# wb_imx233_core_rev_c3.net
KiCad netlist of a schematic drawn in EAGLE
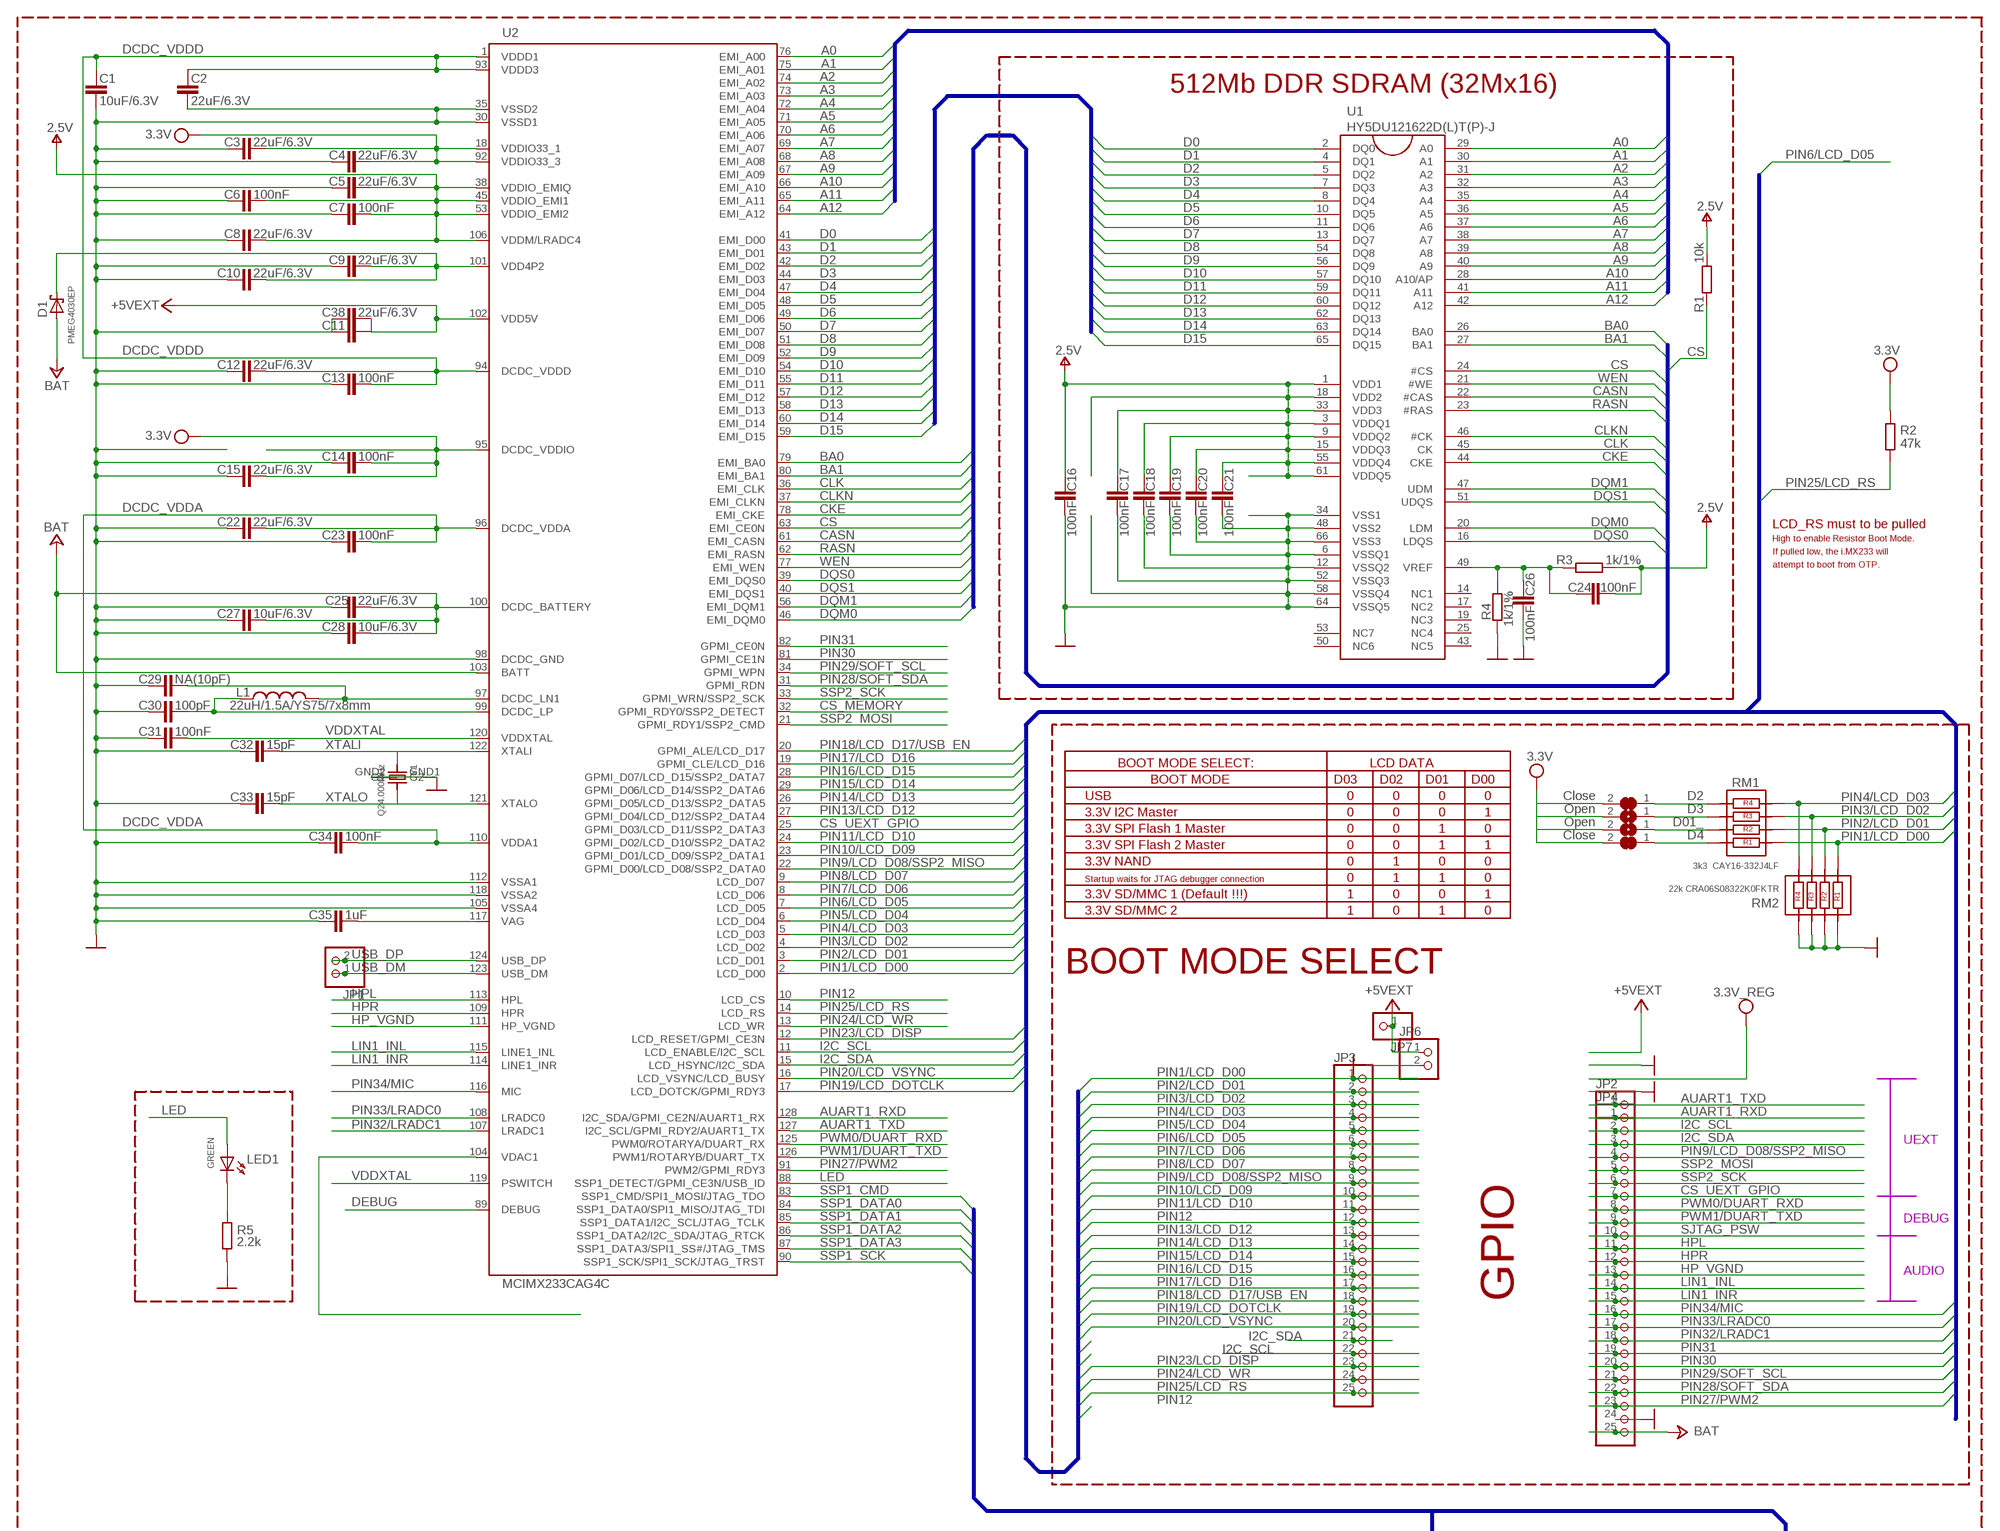
[diagram p0: schematic, sheet 1, part 1 of 2]
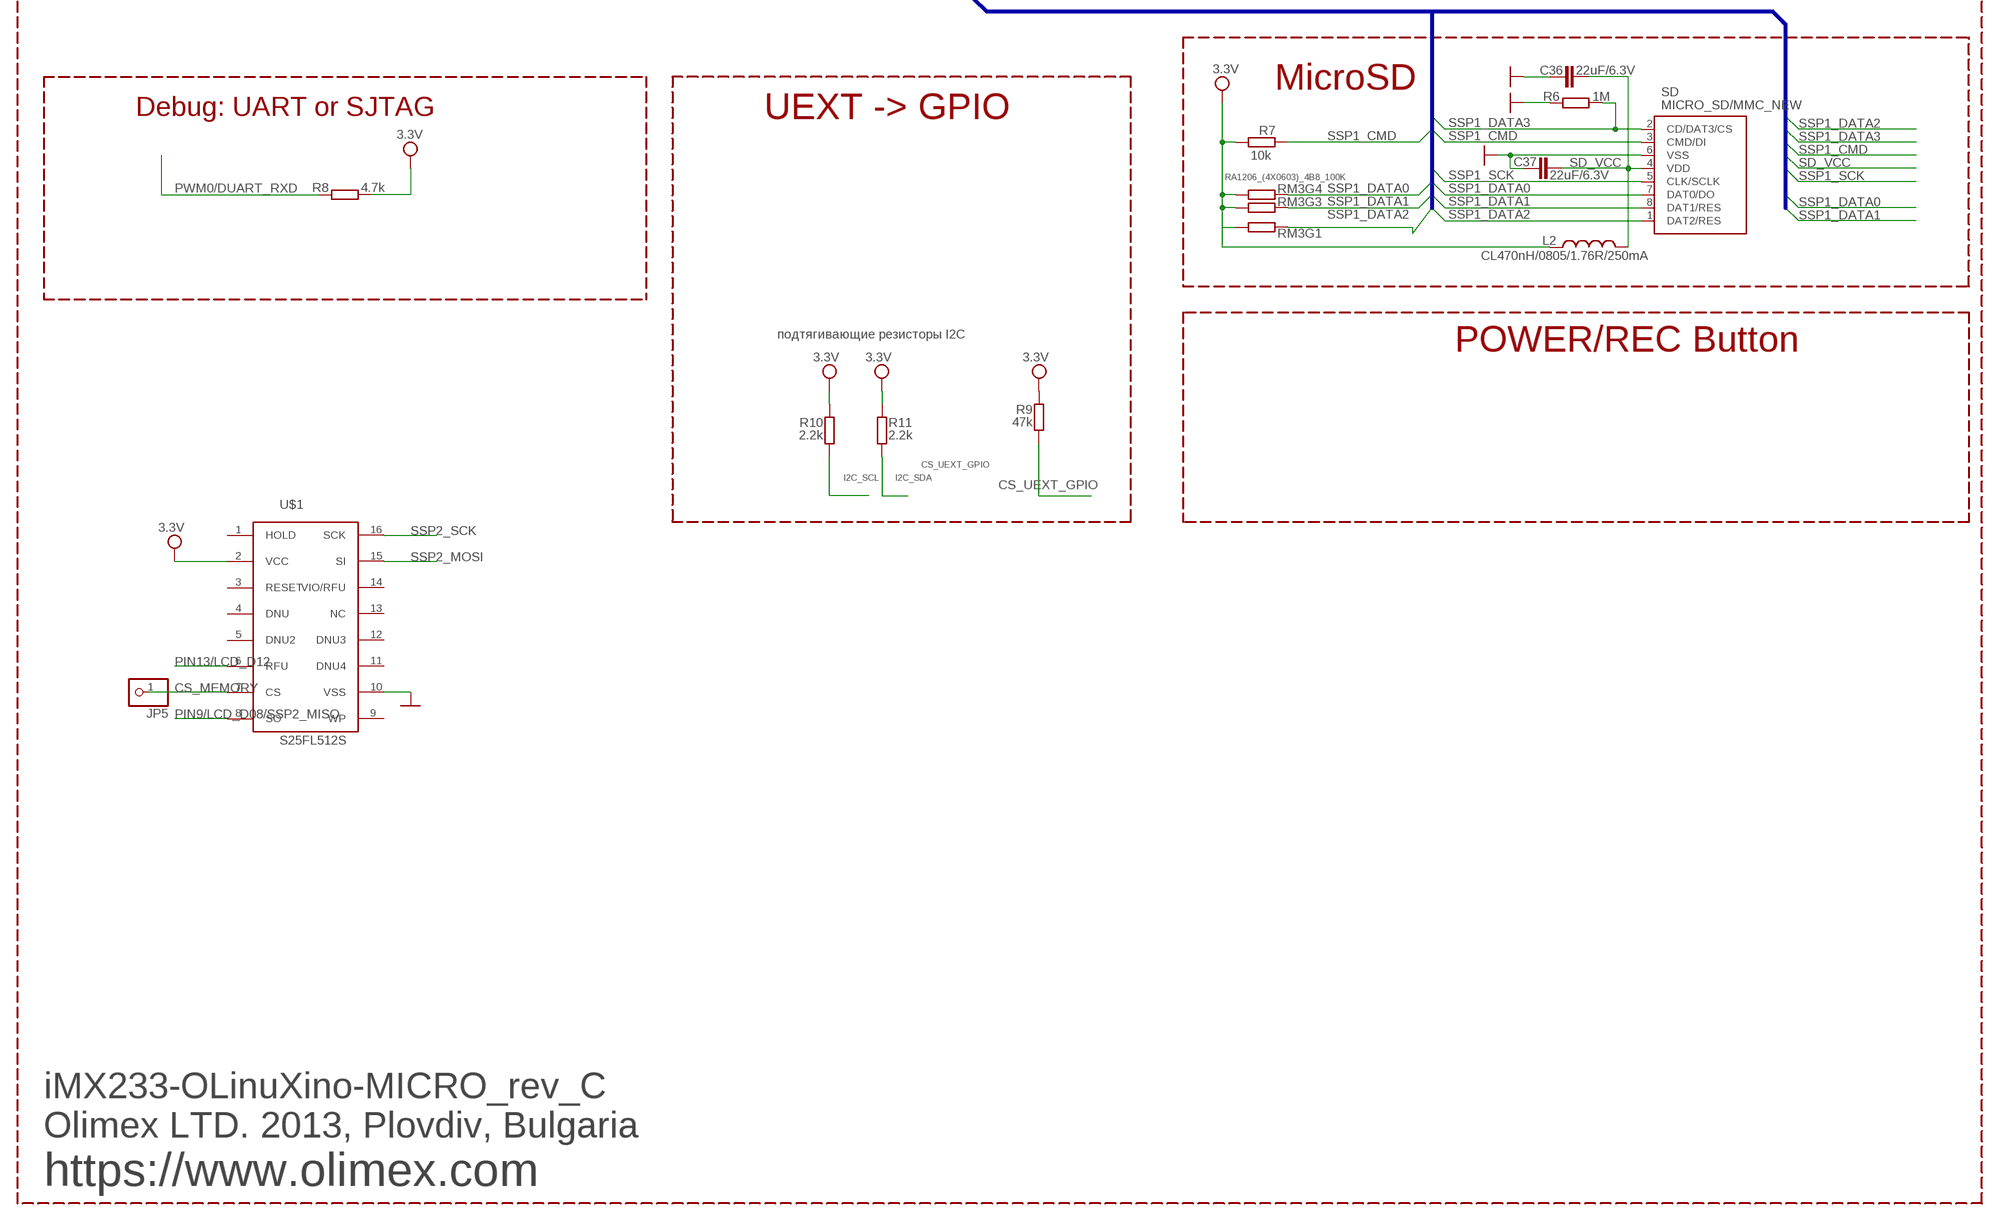
[diagram p1: schematic, sheet 1, part 2 of 2]

(export (version "E")
  (design (tool "Eeschema 10.0.6"))
  (components
    (comp (ref "C1")
      (value "10uF/6.3V")
      (footprint "eagle-import:C0603_DWS")
      (libsource (lib "eagle-import") (part "C-EUC0603_DWS"))
    )
    (comp (ref "C2")
      (value "22uF/6.3V")
      (footprint "eagle-import:C0603_DWS")
      (libsource (lib "eagle-import") (part "C-EUC0603_DWS"))
    )
    (comp (ref "C3")
      (value "22uF/6.3V")
      (footprint "eagle-import:C0603_DWS")
      (libsource (lib "eagle-import") (part "C-EUC0603_DWS"))
    )
    (comp (ref "C4")
      (value "22uF/6.3V")
      (footprint "eagle-import:C0603_DWS")
      (libsource (lib "eagle-import") (part "C-EUC0603_DWS"))
    )
    (comp (ref "C5")
      (value "22uF/6.3V")
      (footprint "eagle-import:C0603_DWS")
      (libsource (lib "eagle-import") (part "C-EUC0603_DWS"))
    )
    (comp (ref "C6")
      (value "100nF")
      (footprint "eagle-import:C0603_DWS")
      (libsource (lib "eagle-import") (part "C-EUC0603_DWS"))
    )
    (comp (ref "C7")
      (value "100nF")
      (footprint "eagle-import:C0603_DWS")
      (libsource (lib "eagle-import") (part "C-EUC0603_DWS"))
    )
    (comp (ref "C8")
      (value "22uF/6.3V")
      (footprint "eagle-import:C0603_DWS")
      (libsource (lib "eagle-import") (part "C-EUC0603_DWS"))
    )
    (comp (ref "C9")
      (value "22uF/6.3V")
      (footprint "eagle-import:C0603_DWS")
      (libsource (lib "eagle-import") (part "C-EUC0603_DWS"))
    )
    (comp (ref "C10")
      (value "22uF/6.3V")
      (footprint "eagle-import:C0603_DWS")
      (libsource (lib "eagle-import") (part "C-EUC0603_DWS"))
    )
    (comp (ref "C11")
      (value "100nF")
      (footprint "eagle-import:C0603_DWS")
      (libsource (lib "eagle-import") (part "C-EUC0603_DWS"))
    )
    (comp (ref "C12")
      (value "22uF/6.3V")
      (footprint "eagle-import:C0603_DWS")
      (libsource (lib "eagle-import") (part "C-EUC0603_DWS"))
    )
    (comp (ref "C13")
      (value "100nF")
      (footprint "eagle-import:C0603_DWS")
      (libsource (lib "eagle-import") (part "C-EUC0603_DWS"))
    )
    (comp (ref "C14")
      (value "100nF")
      (footprint "eagle-import:C0603_DWS")
      (libsource (lib "eagle-import") (part "C-EUC0603_DWS"))
    )
    (comp (ref "C15")
      (value "22uF/6.3V")
      (footprint "eagle-import:C0603_DWS")
      (libsource (lib "eagle-import") (part "C-EUC0603_DWS"))
    )
    (comp (ref "C16")
      (value "100nF")
      (footprint "eagle-import:C0603_DWS")
      (libsource (lib "eagle-import") (part "C-EUC0603_DWS"))
    )
    (comp (ref "C17")
      (value "100nF")
      (footprint "eagle-import:C0603_DWS")
      (libsource (lib "eagle-import") (part "C-EUC0603_DWS"))
    )
    (comp (ref "C18")
      (value "100nF")
      (footprint "eagle-import:C0603_DWS")
      (libsource (lib "eagle-import") (part "C-EUC0603_DWS"))
    )
    (comp (ref "C19")
      (value "100nF")
      (footprint "eagle-import:C0603_DWS")
      (libsource (lib "eagle-import") (part "C-EUC0603_DWS"))
    )
    (comp (ref "C20")
      (value "100nF")
      (footprint "eagle-import:C0603_DWS")
      (libsource (lib "eagle-import") (part "C-EUC0603_DWS"))
    )
    (comp (ref "C21")
      (value "100nF")
      (footprint "eagle-import:C0603_DWS")
      (libsource (lib "eagle-import") (part "C-EUC0603_DWS"))
    )
    (comp (ref "C22")
      (value "22uF/6.3V")
      (footprint "eagle-import:C0603_DWS")
      (libsource (lib "eagle-import") (part "C-EUC0603_DWS"))
    )
    (comp (ref "C23")
      (value "100nF")
      (footprint "eagle-import:C0603_DWS")
      (libsource (lib "eagle-import") (part "C-EUC0603_DWS"))
    )
    (comp (ref "C24")
      (value "100nF")
      (footprint "eagle-import:C0603_DWS")
      (libsource (lib "eagle-import") (part "C-EUC0603_DWS"))
    )
    (comp (ref "C25")
      (value "22uF/6.3V")
      (footprint "eagle-import:C0603_DWS")
      (libsource (lib "eagle-import") (part "C-EUC0603_DWS"))
    )
    (comp (ref "C26")
      (value "100nF")
      (footprint "eagle-import:C0603_DWS")
      (libsource (lib "eagle-import") (part "C-EUC0603_DWS"))
    )
    (comp (ref "C27")
      (value "10uF/6.3V")
      (footprint "eagle-import:C0603_DWS")
      (libsource (lib "eagle-import") (part "C-EUC0603_DWS"))
    )
    (comp (ref "C28")
      (value "10uF/6.3V")
      (footprint "eagle-import:C0603_DWS")
      (libsource (lib "eagle-import") (part "C-EUC0603_DWS"))
    )
    (comp (ref "C29")
      (value "NA(10pF)")
      (footprint "eagle-import:C0603_DWS")
      (libsource (lib "eagle-import") (part "C-EUC0603_DWS"))
    )
    (comp (ref "C30")
      (value "100pF")
      (footprint "eagle-import:C0603_DWS")
      (libsource (lib "eagle-import") (part "C-EUC0603_DWS"))
    )
    (comp (ref "C31")
      (value "100nF")
      (footprint "eagle-import:C0603_DWS")
      (libsource (lib "eagle-import") (part "C-EUC0603_DWS"))
    )
    (comp (ref "C32")
      (value "15pF")
      (footprint "eagle-import:C0603_DWS")
      (libsource (lib "eagle-import") (part "C-EUC0603_DWS"))
    )
    (comp (ref "C33")
      (value "15pF")
      (footprint "eagle-import:C0603_DWS")
      (libsource (lib "eagle-import") (part "C-EUC0603_DWS"))
    )
    (comp (ref "C34")
      (value "100nF")
      (footprint "eagle-import:C0603_DWS")
      (libsource (lib "eagle-import") (part "C-EUC0603_DWS"))
    )
    (comp (ref "C35")
      (value "1uF")
      (footprint "eagle-import:C0603_DWS")
      (libsource (lib "eagle-import") (part "C-EUC0603_DWS"))
    )
    (comp (ref "C36")
      (value "22uF/6.3V")
      (footprint "eagle-import:C0603_DWS")
      (libsource (lib "eagle-import") (part "C-EUC0603_DWS"))
    )
    (comp (ref "C37")
      (value "22uF/6.3V")
      (footprint "eagle-import:C0603_DWS")
      (libsource (lib "eagle-import") (part "C-EUC0603_DWS"))
    )
    (comp (ref "C38")
      (value "22uF/6.3V")
      (footprint "eagle-import:C0603_DWS")
      (libsource (lib "eagle-import") (part "C-EUC0603_DWS"))
    )
    (comp (ref "D1")
      (value "PMEG4030EP")
      (footprint "eagle-import:MLL-41")
      (libsource (lib "eagle-import") (part "SCHOTKKY7.62SS2"))
    )
    (comp (ref "D01_")
      (value "Open")
      (footprint "eagle-import:SJ_1_SMALLER")
      (libsource (lib "eagle-import") (part "SJSJ_SMALLER"))
    )
    (comp (ref "D2")
      (value "Close")
      (footprint "eagle-import:SJ_1_SMALLER")
      (libsource (lib "eagle-import") (part "SJSJ_SMALLER"))
    )
    (comp (ref "D3")
      (value "Open")
      (footprint "eagle-import:SJ_1_SMALLER")
      (libsource (lib "eagle-import") (part "SJSJ_SMALLER"))
    )
    (comp (ref "D4")
      (value "Close")
      (footprint "eagle-import:SJ_1_SMALLER")
      (libsource (lib "eagle-import") (part "SJSJ_SMALLER"))
    )
    (comp (ref "JP1")
      (value "PINHD-1X2")
      (footprint "eagle-import:1X02-R")
      (libsource (lib "eagle-import") (part "PINHD-1X2"))
    )
    (comp (ref "JP2")
      (value "PINHD-1X1")
      (footprint "eagle-import:1X01")
      (libsource (lib "eagle-import") (part "PINHD-1X1"))
    )
    (comp (ref "JP3")
      (value "PINHD-1X25")
      (footprint "eagle-import:1X25")
      (libsource (lib "eagle-import") (part "PINHD-1X25"))
    )
    (comp (ref "JP4")
      (value "PINHD-1X25")
      (footprint "eagle-import:1X25")
      (libsource (lib "eagle-import") (part "PINHD-1X25"))
    )
    (comp (ref "JP5")
      (value "PINHD-1X1")
      (footprint "eagle-import:1X01")
      (libsource (lib "eagle-import") (part "PINHD-1X1"))
    )
    (comp (ref "JP6")
      (value "PINHD-1X2")
      (footprint "eagle-import:1X02-R")
      (libsource (lib "eagle-import") (part "PINHD-1X2"))
    )
    (comp (ref "JP7")
      (value "PINHD-1X1")
      (footprint "eagle-import:1X01")
      (libsource (lib "eagle-import") (part "PINHD-1X1"))
    )
    (comp (ref "L1")
      (value "22uH/1.5A/YS75/7x8mm")
      (footprint "eagle-import:L7078")
      (libsource (lib "eagle-import") (part "L-USL7078"))
    )
    (comp (ref "L2")
      (value "CL470nH/0805/1.76R/250mA")
      (footprint "eagle-import:L0805_5MIL_DWS")
      (libsource (lib "eagle-import") (part "L-USL0805_5MIL_DWS"))
    )
    (comp (ref "LED1")
      (value "GREEN")
      (footprint "eagle-import:LED-0805")
      (libsource (lib "eagle-import") (part "LED0805DWS"))
    )
    (comp (ref "R1")
      (value "10k")
      (footprint "eagle-import:R0603_5MIL_DWS")
      (libsource (lib "eagle-import") (part "R-EU_R0603_5MIL_DWS"))
    )
    (comp (ref "R2")
      (value "47k")
      (footprint "eagle-import:R0603_5MIL_DWS")
      (libsource (lib "eagle-import") (part "R-EU_R0603_5MIL_DWS"))
    )
    (comp (ref "R3")
      (value "1k/1%")
      (footprint "eagle-import:R0603_5MIL_DWS")
      (libsource (lib "eagle-import") (part "R-EU_R0603_5MIL_DWS"))
    )
    (comp (ref "R4")
      (value "1k/1%")
      (footprint "eagle-import:R0603_5MIL_DWS")
      (libsource (lib "eagle-import") (part "R-EU_R0603_5MIL_DWS"))
    )
    (comp (ref "R5")
      (value "2.2k")
      (footprint "eagle-import:R0603_5MIL_DWS")
      (libsource (lib "eagle-import") (part "R-EU_R0603_5MIL_DWS"))
    )
    (comp (ref "R6")
      (value "1M")
      (footprint "eagle-import:R0603_5MIL_DWS")
      (libsource (lib "eagle-import") (part "R-EU_R0603_5MIL_DWS"))
    )
    (comp (ref "R7")
      (value "10k")
      (footprint "eagle-import:R0603_5MIL_DWS")
      (libsource (lib "eagle-import") (part "R-EU_R0603_5MIL_DWS"))
    )
    (comp (ref "R8")
      (value "4.7k")
      (footprint "eagle-import:R0603_5MIL_DWS")
      (libsource (lib "eagle-import") (part "R-EU_R0603_5MIL_DWS"))
    )
    (comp (ref "R9")
      (value "47k")
      (footprint "eagle-import:R0603_5MIL_DWS")
      (libsource (lib "eagle-import") (part "R-EU_R0603_5MIL_DWS"))
    )
    (comp (ref "R10")
      (value "2.2k")
      (footprint "eagle-import:R0603_5MIL_DWS")
      (libsource (lib "eagle-import") (part "R-EU_R0603_5MIL_DWS"))
    )
    (comp (ref "R11")
      (value "2.2k")
      (footprint "eagle-import:R0603_5MIL_DWS")
      (libsource (lib "eagle-import") (part "R-EU_R0603_5MIL_DWS"))
    )
    (comp (ref "RM1")
      (value "3k3 CAY16-332J4LF")
      (footprint "eagle-import:R_MATRIX_4")
      (libsource (lib "eagle-import") (part "R_MATRIX_4"))
    )
    (comp (ref "RM2")
      (value "22k CRA06S08322K0FKTR")
      (footprint "eagle-import:R_MATRIX_4")
      (libsource (lib "eagle-import") (part "R_MATRIX_4"))
    )
    (comp (ref "RM3")
      (value "RA1206_(4X0603)_4B8_100K")
      (footprint "eagle-import:R_MATRIX_4")
      (libsource (lib "eagle-import") (part "R_MATRIX_4E"))
    )
    (comp (ref "SD")
      (value "MICRO_SD/MMC_NEW")
      (footprint "eagle-import:TFR_C-MEM-CON")
      (libsource (lib "eagle-import") (part "MICRO_SD/MMC_NEW"))
    )
    (comp (ref "U$1")
      (value "S25FL512S")
      (footprint "eagle-import:1")
      (libsource (lib "eagle-import") (part "S25FL512S"))
    )
    (comp (ref "U1")
      (value "HY5DU121622D(L)T(P)-J")
      (footprint "eagle-import:66TSOP-II")
      (libsource (lib "eagle-import") (part "HY5DU121622D(L)T(P)-J"))
    )
    (comp (ref "U2")
      (value "MCIMX233CAG4C")
      (footprint "eagle-import:TQFP128LD")
      (libsource (lib "eagle-import") (part "MCIMX233DAG4B_LD"))
    )
    (comp (ref "Y1")
      (value "Q24.000MHz")
      (footprint "eagle-import:CRYSTAL_3.2X2.5")
      (libsource (lib "eagle-import") (part "CRYSTALTHIN"))
    )
  )
  (nets
    (net (code "1") (name "+5VEXT") (class "Default")
      (node (ref "C11") (pin "2") (pinfunction "2_2") (pintype "passive"))
      (node (ref "C38") (pin "2") (pinfunction "2_2") (pintype "passive"))
      (node (ref "JP6") (pin "1") (pinfunction "1_1") (pintype "passive"))
      (node (ref "JP7") (pin "1") (pinfunction "1_1") (pintype "passive"))
      (node (ref "U2") (pin "102") (pinfunction "VDD5V_102") (pintype "power_in"))
    )
    (net (code "2") (name "/A0") (class "Default")
      (node (ref "U1") (pin "29") (pinfunction "A0_29") (pintype "input"))
      (node (ref "U2") (pin "76") (pinfunction "EMI_A00_76") (pintype "bidirectional"))
    )
    (net (code "3") (name "/A1") (class "Default")
      (node (ref "U1") (pin "30") (pinfunction "A1_30") (pintype "input"))
      (node (ref "U2") (pin "75") (pinfunction "EMI_A01_75") (pintype "bidirectional"))
    )
    (net (code "4") (name "/A2") (class "Default")
      (node (ref "U1") (pin "31") (pinfunction "A2_31") (pintype "input"))
      (node (ref "U2") (pin "74") (pinfunction "EMI_A02_74") (pintype "bidirectional"))
    )
    (net (code "5") (name "/A3") (class "Default")
      (node (ref "U1") (pin "32") (pinfunction "A3_32") (pintype "input"))
      (node (ref "U2") (pin "73") (pinfunction "EMI_A03_73") (pintype "bidirectional"))
    )
    (net (code "6") (name "/A4") (class "Default")
      (node (ref "U1") (pin "35") (pinfunction "A4_35") (pintype "input"))
      (node (ref "U2") (pin "72") (pinfunction "EMI_A04_72") (pintype "bidirectional"))
    )
    (net (code "7") (name "/A5") (class "Default")
      (node (ref "U1") (pin "36") (pinfunction "A5_36") (pintype "input"))
      (node (ref "U2") (pin "71") (pinfunction "EMI_A05_71") (pintype "bidirectional"))
    )
    (net (code "8") (name "/A6") (class "Default")
      (node (ref "U1") (pin "37") (pinfunction "A6_37") (pintype "input"))
      (node (ref "U2") (pin "70") (pinfunction "EMI_A06_70") (pintype "bidirectional"))
    )
    (net (code "9") (name "/A7") (class "Default")
      (node (ref "U1") (pin "38") (pinfunction "A7_38") (pintype "input"))
      (node (ref "U2") (pin "69") (pinfunction "EMI_A07_69") (pintype "bidirectional"))
    )
    (net (code "10") (name "/A8") (class "Default")
      (node (ref "U1") (pin "39") (pinfunction "A8_39") (pintype "input"))
      (node (ref "U2") (pin "68") (pinfunction "EMI_A08_68") (pintype "bidirectional"))
    )
    (net (code "11") (name "/A9") (class "Default")
      (node (ref "U1") (pin "40") (pinfunction "A9_40") (pintype "input"))
      (node (ref "U2") (pin "67") (pinfunction "EMI_A09_67") (pintype "bidirectional"))
    )
    (net (code "12") (name "/A10") (class "Default")
      (node (ref "U1") (pin "28") (pinfunction "A10/AP_28") (pintype "input"))
      (node (ref "U2") (pin "66") (pinfunction "EMI_A10_66") (pintype "bidirectional"))
    )
    (net (code "13") (name "/A11") (class "Default")
      (node (ref "U1") (pin "41") (pinfunction "A11_41") (pintype "input"))
      (node (ref "U2") (pin "65") (pinfunction "EMI_A11_65") (pintype "bidirectional"))
    )
    (net (code "14") (name "/A12") (class "Default")
      (node (ref "U1") (pin "42") (pinfunction "A12_42") (pintype "input"))
      (node (ref "U2") (pin "64") (pinfunction "EMI_A12_64") (pintype "bidirectional"))
    )
    (net (code "15") (name "/AUART1_RXD") (class "Default")
      (node (ref "JP4") (pin "1") (pinfunction "1_1") (pintype "passive"))
      (node (ref "U2") (pin "128") (pinfunction "I2C_SDA/GPMI_CE2N/AUART1_RX_128") (pintype "bidirectional"))
    )
    (net (code "16") (name "/AUART1_TXD") (class "Default")
      (node (ref "JP2") (pin "1") (pinfunction "1_1") (pintype "passive"))
      (node (ref "U2") (pin "127") (pinfunction "I2C_SCL/GPMI_RDY2/AUART1_TX_127") (pintype "bidirectional"))
    )
    (net (code "17") (name "/BA0") (class "Default")
      (node (ref "U1") (pin "26") (pinfunction "BA0_26") (pintype "input"))
      (node (ref "U2") (pin "79") (pinfunction "EMI_BA0_79") (pintype "output"))
    )
    (net (code "18") (name "/BA1") (class "Default")
      (node (ref "U1") (pin "27") (pinfunction "BA1_27") (pintype "input"))
      (node (ref "U2") (pin "80") (pinfunction "EMI_BA1_80") (pintype "output"))
    )
    (net (code "19") (name "/CASN") (class "Default")
      (node (ref "U1") (pin "22") (pinfunction "#CAS_22") (pintype "input"))
      (node (ref "U2") (pin "61") (pinfunction "EMI_CASN_61") (pintype "output"))
    )
    (net (code "20") (name "/CKE") (class "Default")
      (node (ref "U1") (pin "44") (pinfunction "CKE_44") (pintype "input"))
      (node (ref "U2") (pin "78") (pinfunction "EMI_CKE_78") (pintype "output"))
    )
    (net (code "21") (name "/CLK") (class "Default")
      (node (ref "U1") (pin "45") (pinfunction "CK_45") (pintype "input"))
      (node (ref "U2") (pin "36") (pinfunction "EMI_CLK_36") (pintype "output"))
    )
    (net (code "22") (name "/CLKN") (class "Default")
      (node (ref "U1") (pin "46") (pinfunction "#CK_46") (pintype "input"))
      (node (ref "U2") (pin "37") (pinfunction "EMI_CLKN_37") (pintype "output"))
    )
    (net (code "23") (name "/CS") (class "Default")
      (node (ref "R1") (pin "1") (pinfunction "1_1") (pintype "passive"))
      (node (ref "U1") (pin "24") (pinfunction "#CS_24") (pintype "input"))
      (node (ref "U2") (pin "63") (pinfunction "EMI_CE0N_63") (pintype "output"))
    )
    (net (code "24") (name "/CS_MEMORY") (class "Default")
      (node (ref "JP5") (pin "1") (pinfunction "1_1") (pintype "passive"))
      (node (ref "U$1") (pin "7") (pinfunction "CS_7") (pintype "bidirectional"))
      (node (ref "U2") (pin "32") (pinfunction "GPMI_RDY0/SSP2_DETECT_32") (pintype "bidirectional"))
    )
    (net (code "25") (name "/CS_UEXT_GPIO") (class "Default")
      (node (ref "JP4") (pin "7") (pinfunction "7_7") (pintype "passive"))
      (node (ref "R9") (pin "1") (pinfunction "1_1") (pintype "passive"))
      (node (ref "U2") (pin "25") (pinfunction "GPMI_D03/LCD_D11/SSP2_DATA3_25") (pintype "bidirectional"))
    )
    (net (code "26") (name "/D0") (class "Default")
      (node (ref "U1") (pin "2") (pinfunction "DQ0_2") (pintype "bidirectional"))
      (node (ref "U2") (pin "41") (pinfunction "EMI_D00_41") (pintype "bidirectional"))
    )
    (net (code "27") (name "/D1") (class "Default")
      (node (ref "U1") (pin "4") (pinfunction "DQ1_4") (pintype "bidirectional"))
      (node (ref "U2") (pin "43") (pinfunction "EMI_D01_43") (pintype "bidirectional"))
    )
    (net (code "28") (name "/D2") (class "Default")
      (node (ref "U1") (pin "5") (pinfunction "DQ2_5") (pintype "bidirectional"))
      (node (ref "U2") (pin "42") (pinfunction "EMI_D02_42") (pintype "bidirectional"))
    )
    (net (code "29") (name "/D3") (class "Default")
      (node (ref "U1") (pin "7") (pinfunction "DQ3_7") (pintype "bidirectional"))
      (node (ref "U2") (pin "44") (pinfunction "EMI_D03_44") (pintype "bidirectional"))
    )
    (net (code "30") (name "/D4") (class "Default")
      (node (ref "U1") (pin "8") (pinfunction "DQ4_8") (pintype "bidirectional"))
      (node (ref "U2") (pin "47") (pinfunction "EMI_D04_47") (pintype "bidirectional"))
    )
    (net (code "31") (name "/D5") (class "Default")
      (node (ref "U1") (pin "10") (pinfunction "DQ5_10") (pintype "bidirectional"))
      (node (ref "U2") (pin "48") (pinfunction "EMI_D05_48") (pintype "bidirectional"))
    )
    (net (code "32") (name "/D6") (class "Default")
      (node (ref "U1") (pin "11") (pinfunction "DQ6_11") (pintype "bidirectional"))
      (node (ref "U2") (pin "49") (pinfunction "EMI_D06_49") (pintype "bidirectional"))
    )
    (net (code "33") (name "/D7") (class "Default")
      (node (ref "U1") (pin "13") (pinfunction "DQ7_13") (pintype "bidirectional"))
      (node (ref "U2") (pin "50") (pinfunction "EMI_D07_50") (pintype "bidirectional"))
    )
    (net (code "34") (name "/D8") (class "Default")
      (node (ref "U1") (pin "54") (pinfunction "DQ8_54") (pintype "bidirectional"))
      (node (ref "U2") (pin "51") (pinfunction "EMI_D08_51") (pintype "bidirectional"))
    )
    (net (code "35") (name "/D9") (class "Default")
      (node (ref "U1") (pin "56") (pinfunction "DQ9_56") (pintype "bidirectional"))
      (node (ref "U2") (pin "52") (pinfunction "EMI_D09_52") (pintype "bidirectional"))
    )
    (net (code "36") (name "/D10") (class "Default")
      (node (ref "U1") (pin "57") (pinfunction "DQ10_57") (pintype "bidirectional"))
      (node (ref "U2") (pin "54") (pinfunction "EMI_D10_54") (pintype "bidirectional"))
    )
    (net (code "37") (name "/D11") (class "Default")
      (node (ref "U1") (pin "59") (pinfunction "DQ11_59") (pintype "bidirectional"))
      (node (ref "U2") (pin "55") (pinfunction "EMI_D11_55") (pintype "bidirectional"))
    )
    (net (code "38") (name "/D12") (class "Default")
      (node (ref "U1") (pin "60") (pinfunction "DQ12_60") (pintype "bidirectional"))
      (node (ref "U2") (pin "57") (pinfunction "EMI_D12_57") (pintype "bidirectional"))
    )
    (net (code "39") (name "/D13") (class "Default")
      (node (ref "U1") (pin "62") (pinfunction "DQ13_62") (pintype "bidirectional"))
      (node (ref "U2") (pin "58") (pinfunction "EMI_D13_58") (pintype "bidirectional"))
    )
    (net (code "40") (name "/D14") (class "Default")
      (node (ref "U1") (pin "63") (pinfunction "DQ14_63") (pintype "bidirectional"))
      (node (ref "U2") (pin "60") (pinfunction "EMI_D14_60") (pintype "bidirectional"))
    )
    (net (code "41") (name "/D15") (class "Default")
      (node (ref "U1") (pin "65") (pinfunction "DQ15_65") (pintype "bidirectional"))
      (node (ref "U2") (pin "59") (pinfunction "EMI_D15_59") (pintype "bidirectional"))
    )
    (net (code "42") (name "/DCDC_VDDA") (class "Default")
      (node (ref "C22") (pin "2") (pinfunction "2_2") (pintype "passive"))
      (node (ref "C23") (pin "2") (pinfunction "2_2") (pintype "passive"))
      (node (ref "C34") (pin "2") (pinfunction "2_2") (pintype "passive"))
      (node (ref "U2") (pin "110") (pinfunction "VDDA1_110") (pintype "power_in"))
      (node (ref "U2") (pin "96") (pinfunction "DCDC_VDDA_96") (pintype "power_in"))
    )
    (net (code "43") (name "/DCDC_VDDD") (class "Default")
      (node (ref "C1") (pin "2") (pinfunction "2_2") (pintype "passive"))
      (node (ref "C12") (pin "2") (pinfunction "2_2") (pintype "passive"))
      (node (ref "C13") (pin "2") (pinfunction "2_2") (pintype "passive"))
      (node (ref "C2") (pin "2") (pinfunction "2_2") (pintype "passive"))
      (node (ref "U2") (pin "1") (pinfunction "VDDD1_1") (pintype "power_in"))
      (node (ref "U2") (pin "93") (pinfunction "VDDD3_93") (pintype "power_in"))
      (node (ref "U2") (pin "94") (pinfunction "DCDC_VDDD_94") (pintype "power_in"))
    )
    (net (code "44") (name "/DEBUG") (class "Default")
      (node (ref "U2") (pin "89") (pinfunction "DEBUG_89") (pintype "bidirectional"))
    )
    (net (code "45") (name "/DQM0") (class "Default")
      (node (ref "U1") (pin "20") (pinfunction "LDM_20") (pintype "input"))
      (node (ref "U2") (pin "46") (pinfunction "EMI_DQM0_46") (pintype "output"))
    )
    (net (code "46") (name "/DQM1") (class "Default")
      (node (ref "U1") (pin "47") (pinfunction "UDM_47") (pintype "input"))
      (node (ref "U2") (pin "56") (pinfunction "EMI_DQM1_56") (pintype "output"))
    )
    (net (code "47") (name "/DQS0") (class "Default")
      (node (ref "U1") (pin "16") (pinfunction "LDQS_16") (pintype "bidirectional"))
      (node (ref "U2") (pin "39") (pinfunction "EMI_DQS0_39") (pintype "output"))
    )
    (net (code "48") (name "/DQS1") (class "Default")
      (node (ref "U1") (pin "51") (pinfunction "UDQS_51") (pintype "input"))
      (node (ref "U2") (pin "40") (pinfunction "EMI_DQS1_40") (pintype "output"))
    )
    (net (code "49") (name "/HPL") (class "Default")
      (node (ref "JP4") (pin "11") (pinfunction "11_11") (pintype "passive"))
      (node (ref "U2") (pin "113") (pinfunction "HPL_113") (pintype "output"))
    )
    (net (code "50") (name "/HPR") (class "Default")
      (node (ref "JP4") (pin "12") (pinfunction "12_12") (pintype "passive"))
      (node (ref "U2") (pin "109") (pinfunction "HPR_109") (pintype "output"))
    )
    (net (code "51") (name "/HP_VGND") (class "Default")
      (node (ref "JP4") (pin "13") (pinfunction "13_13") (pintype "passive"))
      (node (ref "U2") (pin "111") (pinfunction "HP_VGND_111") (pintype "power_in"))
    )
    (net (code "52") (name "/I2C_SCL") (class "Default")
      (node (ref "JP3") (pin "22") (pinfunction "22_22") (pintype "passive"))
      (node (ref "JP4") (pin "2") (pinfunction "2_2") (pintype "passive"))
      (node (ref "R10") (pin "1") (pinfunction "1_1") (pintype "passive"))
      (node (ref "U2") (pin "11") (pinfunction "LCD_ENABLE/I2C_SCL_11") (pintype "bidirectional"))
    )
    (net (code "53") (name "/I2C_SDA") (class "Default")
      (node (ref "JP3") (pin "21") (pinfunction "21_21") (pintype "passive"))
      (node (ref "JP4") (pin "3") (pinfunction "3_3") (pintype "passive"))
      (node (ref "R11") (pin "1") (pinfunction "1_1") (pintype "passive"))
      (node (ref "U2") (pin "15") (pinfunction "LCD_HSYNC/I2C_SDA_15") (pintype "bidirectional"))
    )
    (net (code "54") (name "/LED") (class "Default")
      (node (ref "LED1") (pin "A") (pinfunction "A_A") (pintype "passive"))
      (node (ref "U2") (pin "88") (pinfunction "SSP1_DETECT/GPMI_CE3N/USB_ID_88") (pintype "bidirectional"))
    )
    (net (code "55") (name "/LIN1_INL") (class "Default")
      (node (ref "JP4") (pin "14") (pinfunction "14_14") (pintype "passive"))
      (node (ref "U2") (pin "115") (pinfunction "LINE1_INL_115") (pintype "input"))
    )
    (net (code "56") (name "/LIN1_INR") (class "Default")
      (node (ref "JP4") (pin "15") (pinfunction "15_15") (pintype "passive"))
      (node (ref "U2") (pin "114") (pinfunction "LINE1_INR_114") (pintype "input"))
    )
    (net (code "57") (name "/PIN1{slash}LCD_D00") (class "Default")
      (node (ref "JP3") (pin "1") (pinfunction "1_1") (pintype "passive"))
      (node (ref "RM1") (pin "1.2") (pinfunction "1.2_1.2") (pintype "passive"))
      (node (ref "RM2") (pin "1.1") (pinfunction "1.1_1.1") (pintype "passive"))
      (node (ref "U2") (pin "2") (pinfunction "LCD_D00_2") (pintype "bidirectional"))
    )
    (net (code "58") (name "/PIN2{slash}LCD_D01") (class "Default")
      (node (ref "JP3") (pin "2") (pinfunction "2_2") (pintype "passive"))
      (node (ref "RM1") (pin "2.2") (pinfunction "2.2_2.2") (pintype "passive"))
      (node (ref "RM2") (pin "2.1") (pinfunction "2.1_2.1") (pintype "passive"))
      (node (ref "U2") (pin "3") (pinfunction "LCD_D01_3") (pintype "bidirectional"))
    )
    (net (code "59") (name "/PIN3{slash}LCD_D02") (class "Default")
      (node (ref "JP3") (pin "3") (pinfunction "3_3") (pintype "passive"))
      (node (ref "RM1") (pin "3.2") (pinfunction "3.2_3.2") (pintype "passive"))
      (node (ref "RM2") (pin "3.1") (pinfunction "3.1_3.1") (pintype "passive"))
      (node (ref "U2") (pin "4") (pinfunction "LCD_D02_4") (pintype "bidirectional"))
    )
    (net (code "60") (name "/PIN4{slash}LCD_D03") (class "Default")
      (node (ref "JP3") (pin "4") (pinfunction "4_4") (pintype "passive"))
      (node (ref "RM1") (pin "4.2") (pinfunction "4.2_4.2") (pintype "passive"))
      (node (ref "RM2") (pin "4.1") (pinfunction "4.1_4.1") (pintype "passive"))
      (node (ref "U2") (pin "5") (pinfunction "LCD_D03_5") (pintype "bidirectional"))
    )
    (net (code "61") (name "/PIN5{slash}LCD_D04") (class "Default")
      (node (ref "JP3") (pin "5") (pinfunction "5_5") (pintype "passive"))
      (node (ref "U2") (pin "6") (pinfunction "LCD_D04_6") (pintype "bidirectional"))
    )
    (net (code "62") (name "/PIN6{slash}LCD_D05") (class "Default")
      (node (ref "JP3") (pin "6") (pinfunction "6_6") (pintype "passive"))
      (node (ref "U2") (pin "7") (pinfunction "LCD_D05_7") (pintype "bidirectional"))
    )
    (net (code "63") (name "/PIN7{slash}LCD_D06") (class "Default")
      (node (ref "JP3") (pin "7") (pinfunction "7_7") (pintype "passive"))
      (node (ref "U2") (pin "8") (pinfunction "LCD_D06_8") (pintype "bidirectional"))
    )
    (net (code "64") (name "/PIN8{slash}LCD_D07") (class "Default")
      (node (ref "JP3") (pin "8") (pinfunction "8_8") (pintype "passive"))
      (node (ref "U2") (pin "9") (pinfunction "LCD_D07_9") (pintype "bidirectional"))
    )
    (net (code "65") (name "/PIN9{slash}LCD_D08{slash}SSP2_MISO") (class "Default")
      (node (ref "JP3") (pin "9") (pinfunction "9_9") (pintype "passive"))
      (node (ref "JP4") (pin "4") (pinfunction "4_4") (pintype "passive"))
      (node (ref "U$1") (pin "8") (pinfunction "SO_8") (pintype "bidirectional"))
      (node (ref "U2") (pin "22") (pinfunction "GPMI_D00/LCD_D08/SSP2_DATA0_22") (pintype "bidirectional"))
    )
    (net (code "66") (name "/PIN10{slash}LCD_D09") (class "Default")
      (node (ref "JP3") (pin "10") (pinfunction "10_10") (pintype "passive"))
      (node (ref "U2") (pin "23") (pinfunction "GPMI_D01/LCD_D09/SSP2_DATA1_23") (pintype "bidirectional"))
    )
    (net (code "67") (name "/PIN11{slash}LCD_D10") (class "Default")
      (node (ref "JP3") (pin "11") (pinfunction "11_11") (pintype "passive"))
      (node (ref "U2") (pin "24") (pinfunction "GPMI_D02/LCD_D10/SSP2_DATA2_24") (pintype "bidirectional"))
    )
    (net (code "68") (name "/PIN12") (class "Default")
      (node (ref "JP3") (pin "12") (pinfunction "12_12") (pintype "passive"))
      (node (ref "U2") (pin "10") (pinfunction "LCD_CS_10") (pintype "bidirectional"))
    )
    (net (code "69") (name "/PIN13{slash}LCD_D12") (class "Default")
      (node (ref "JP3") (pin "13") (pinfunction "13_13") (pintype "passive"))
      (node (ref "U$1") (pin "6") (pinfunction "RFU_6") (pintype "bidirectional"))
      (node (ref "U2") (pin "27") (pinfunction "GPMI_D04/LCD_D12/SSP2_DATA4_27") (pintype "bidirectional"))
    )
    (net (code "70") (name "/PIN14{slash}LCD_D13") (class "Default")
      (node (ref "JP3") (pin "14") (pinfunction "14_14") (pintype "passive"))
      (node (ref "U2") (pin "26") (pinfunction "GPMI_D05/LCD_D13/SSP2_DATA5_26") (pintype "bidirectional"))
    )
    (net (code "71") (name "/PIN15{slash}LCD_D14") (class "Default")
      (node (ref "JP3") (pin "15") (pinfunction "15_15") (pintype "passive"))
      (node (ref "U2") (pin "29") (pinfunction "GPMI_D06/LCD_D14/SSP2_DATA6_29") (pintype "bidirectional"))
    )
    (net (code "72") (name "/PIN16{slash}LCD_D15") (class "Default")
      (node (ref "JP3") (pin "16") (pinfunction "16_16") (pintype "passive"))
      (node (ref "U2") (pin "28") (pinfunction "GPMI_D07/LCD_D15/SSP2_DATA7_28") (pintype "bidirectional"))
    )
    (net (code "73") (name "/PIN17{slash}LCD_D16") (class "Default")
      (node (ref "JP3") (pin "17") (pinfunction "17_17") (pintype "passive"))
      (node (ref "U2") (pin "19") (pinfunction "GPMI_CLE/LCD_D16_19") (pintype "bidirectional"))
    )
    (net (code "74") (name "/PIN18{slash}LCD_D17{slash}USB_EN") (class "Default")
      (node (ref "JP3") (pin "18") (pinfunction "18_18") (pintype "passive"))
      (node (ref "U2") (pin "20") (pinfunction "GPMI_ALE/LCD_D17_20") (pintype "bidirectional"))
    )
    (net (code "75") (name "/PIN19{slash}LCD_DOTCLK") (class "Default")
      (node (ref "JP3") (pin "19") (pinfunction "19_19") (pintype "passive"))
      (node (ref "U2") (pin "17") (pinfunction "LCD_DOTCK/GPMI_RDY3_17") (pintype "bidirectional"))
    )
    (net (code "76") (name "/PIN20{slash}LCD_VSYNC") (class "Default")
      (node (ref "JP3") (pin "20") (pinfunction "20_20") (pintype "passive"))
      (node (ref "U2") (pin "16") (pinfunction "LCD_VSYNC/LCD_BUSY_16") (pintype "bidirectional"))
    )
    (net (code "77") (name "/PIN23{slash}LCD_DISP") (class "Default")
      (node (ref "JP3") (pin "23") (pinfunction "23_23") (pintype "passive"))
      (node (ref "U2") (pin "12") (pinfunction "LCD_RESET/GPMI_CE3N_12") (pintype "bidirectional"))
    )
    (net (code "78") (name "/PIN24{slash}LCD_WR") (class "Default")
      (node (ref "JP3") (pin "24") (pinfunction "24_24") (pintype "passive"))
      (node (ref "U2") (pin "13") (pinfunction "LCD_WR_13") (pintype "bidirectional"))
    )
    (net (code "79") (name "/PIN25{slash}LCD_RS") (class "Default")
      (node (ref "JP3") (pin "25") (pinfunction "25_25") (pintype "passive"))
      (node (ref "R2") (pin "2") (pinfunction "2_2") (pintype "passive"))
      (node (ref "U2") (pin "14") (pinfunction "LCD_RS_14") (pintype "bidirectional"))
    )
    (net (code "80") (name "/PIN27{slash}PWM2") (class "Default")
      (node (ref "JP4") (pin "23") (pinfunction "23_23") (pintype "passive"))
      (node (ref "U2") (pin "91") (pinfunction "PWM2/GPMI_RDY3_91") (pintype "bidirectional"))
    )
    (net (code "81") (name "/PIN28{slash}SOFT_SDA") (class "Default")
      (node (ref "JP4") (pin "22") (pinfunction "22_22") (pintype "passive"))
      (node (ref "U2") (pin "31") (pinfunction "GPMI_RDN_31") (pintype "bidirectional"))
    )
    (net (code "82") (name "/PIN29{slash}SOFT_SCL") (class "Default")
      (node (ref "JP4") (pin "21") (pinfunction "21_21") (pintype "passive"))
      (node (ref "U2") (pin "34") (pinfunction "GPMI_WPN_34") (pintype "bidirectional"))
    )
    (net (code "83") (name "/PIN30") (class "Default")
      (node (ref "JP4") (pin "20") (pinfunction "20_20") (pintype "passive"))
      (node (ref "U2") (pin "81") (pinfunction "GPMI_CE1N_81") (pintype "bidirectional"))
    )
    (net (code "84") (name "/PIN31") (class "Default")
      (node (ref "JP4") (pin "19") (pinfunction "19_19") (pintype "passive"))
      (node (ref "U2") (pin "82") (pinfunction "GPMI_CE0N_82") (pintype "bidirectional"))
    )
    (net (code "85") (name "/PIN32{slash}LRADC1") (class "Default")
      (node (ref "JP4") (pin "18") (pinfunction "18_18") (pintype "passive"))
      (node (ref "U2") (pin "107") (pinfunction "LRADC1_107") (pintype "bidirectional"))
    )
    (net (code "86") (name "/PIN33{slash}LRADC0") (class "Default")
      (node (ref "JP4") (pin "17") (pinfunction "17_17") (pintype "passive"))
      (node (ref "U2") (pin "108") (pinfunction "LRADC0_108") (pintype "bidirectional"))
    )
    (net (code "87") (name "/PIN34{slash}MIC") (class "Default")
      (node (ref "JP4") (pin "16") (pinfunction "16_16") (pintype "passive"))
      (node (ref "U2") (pin "116") (pinfunction "MIC_116") (pintype "input"))
    )
    (net (code "88") (name "/PWM0{slash}DUART_RXD") (class "Default")
      (node (ref "JP4") (pin "8") (pinfunction "8_8") (pintype "passive"))
      (node (ref "R8") (pin "2") (pinfunction "2_2") (pintype "passive"))
      (node (ref "U2") (pin "125") (pinfunction "PWM0/ROTARYA/DUART_RX_125") (pintype "bidirectional"))
    )
    (net (code "89") (name "/PWM1{slash}DUART_TXD") (class "Default")
      (node (ref "JP4") (pin "9") (pinfunction "9_9") (pintype "passive"))
      (node (ref "U2") (pin "126") (pinfunction "PWM1/ROTARYB/DUART_TX_126") (pintype "bidirectional"))
    )
    (net (code "90") (name "/RASN") (class "Default")
      (node (ref "U1") (pin "23") (pinfunction "#RAS_23") (pintype "input"))
      (node (ref "U2") (pin "62") (pinfunction "EMI_RASN_62") (pintype "output"))
    )
    (net (code "91") (name "/SD_VCC") (class "Default")
      (node (ref "C36") (pin "2") (pinfunction "2_2") (pintype "passive"))
      (node (ref "C37") (pin "2") (pinfunction "2_2") (pintype "passive"))
      (node (ref "L2") (pin "2") (pinfunction "2_2") (pintype "passive"))
      (node (ref "SD") (pin "4") (pinfunction "VDD_4") (pintype "power_in"))
    )
    (net (code "92") (name "/SJTAG_PSW") (class "Default")
      (node (ref "JP4") (pin "10") (pinfunction "10_10") (pintype "passive"))
    )
    (net (code "93") (name "/SSP1_CMD") (class "Default")
      (node (ref "R7") (pin "1") (pinfunction "1_1") (pintype "passive"))
      (node (ref "SD") (pin "3") (pinfunction "CMD/DI_3") (pintype "input"))
      (node (ref "U2") (pin "83") (pinfunction "SSP1_CMD/SPI1_MOSI/JTAG_TDO_83") (pintype "bidirectional"))
    )
    (net (code "94") (name "/SSP1_DATA0") (class "Default")
      (node (ref "RM3") (pin "4.1") (pinfunction "1_4.1") (pintype "passive"))
      (node (ref "SD") (pin "7") (pinfunction "DAT0/DO_7") (pintype "output"))
      (node (ref "U2") (pin "84") (pinfunction "SSP1_DATA0/SPI1_MISO/JTAG_TDI_84") (pintype "bidirectional"))
    )
    (net (code "95") (name "/SSP1_DATA1") (class "Default")
      (node (ref "RM3") (pin "3.1") (pinfunction "1_3.1") (pintype "passive"))
      (node (ref "SD") (pin "8") (pinfunction "DAT1/RES_8") (pintype "bidirectional"))
      (node (ref "U2") (pin "85") (pinfunction "SSP1_DATA1/I2C_SCL/JTAG_TCLK_85") (pintype "bidirectional"))
    )
    (net (code "96") (name "/SSP1_DATA2") (class "Default")
      (node (ref "RM3") (pin "1.1") (pinfunction "1_1.1") (pintype "passive"))
      (node (ref "SD") (pin "1") (pinfunction "DAT2/RES_1") (pintype "bidirectional"))
      (node (ref "U2") (pin "86") (pinfunction "SSP1_DATA2/I2C_SDA/JTAG_RTCK_86") (pintype "bidirectional"))
    )
    (net (code "97") (name "/SSP1_DATA3") (class "Default")
      (node (ref "R6") (pin "1") (pinfunction "1_1") (pintype "passive"))
      (node (ref "SD") (pin "2") (pinfunction "CD/DAT3/CS_2") (pintype "input"))
      (node (ref "U2") (pin "87") (pinfunction "SSP1_DATA3/SPI1_SS#/JTAG_TMS_87") (pintype "bidirectional"))
    )
    (net (code "98") (name "/SSP1_SCK") (class "Default")
      (node (ref "SD") (pin "5") (pinfunction "CLK/SCLK_5") (pintype "input"))
      (node (ref "U2") (pin "90") (pinfunction "SSP1_SCK/SPI1_SCK/JTAG_TRST_90") (pintype "bidirectional"))
    )
    (net (code "99") (name "/SSP2_MOSI") (class "Default")
      (node (ref "JP4") (pin "5") (pinfunction "5_5") (pintype "passive"))
      (node (ref "U$1") (pin "15") (pinfunction "SI_15") (pintype "bidirectional"))
      (node (ref "U2") (pin "21") (pinfunction "GPMI_RDY1/SSP2_CMD_21") (pintype "bidirectional"))
    )
    (net (code "100") (name "/SSP2_SCK") (class "Default")
      (node (ref "JP4") (pin "6") (pinfunction "6_6") (pintype "passive"))
      (node (ref "U$1") (pin "16") (pinfunction "SCK_16") (pintype "bidirectional"))
      (node (ref "U2") (pin "33") (pinfunction "GPMI_WRN/SSP2_SCK_33") (pintype "bidirectional"))
    )
    (net (code "101") (name "/USB_DM") (class "Default")
      (node (ref "JP1") (pin "1") (pinfunction "1_1") (pintype "passive"))
      (node (ref "U2") (pin "123") (pinfunction "USB_DM_123") (pintype "bidirectional"))
    )
    (net (code "102") (name "/USB_DP") (class "Default")
      (node (ref "JP1") (pin "2") (pinfunction "2_2") (pintype "passive"))
      (node (ref "U2") (pin "124") (pinfunction "USB_DP_124") (pintype "bidirectional"))
    )
    (net (code "103") (name "/VDDXTAL") (class "Default")
      (node (ref "C31") (pin "2") (pinfunction "2_2") (pintype "passive"))
      (node (ref "U2") (pin "119") (pinfunction "PSWITCH_119") (pintype "input"))
      (node (ref "U2") (pin "120") (pinfunction "VDDXTAL_120") (pintype "passive"))
    )
    (net (code "104") (name "/WEN") (class "Default")
      (node (ref "U1") (pin "21") (pinfunction "#WE_21") (pintype "input"))
      (node (ref "U2") (pin "77") (pinfunction "EMI_WEN_77") (pintype "output"))
    )
    (net (code "105") (name "/XTALI") (class "Default")
      (node (ref "C32") (pin "2") (pinfunction "2_2") (pintype "passive"))
      (node (ref "U2") (pin "122") (pinfunction "XTALI_122") (pintype "input"))
      (node (ref "Y1") (pin "1") (pinfunction "1_1") (pintype "passive"))
    )
    (net (code "106") (name "/XTALO") (class "Default")
      (node (ref "C33") (pin "2") (pinfunction "2_2") (pintype "passive"))
      (node (ref "U2") (pin "121") (pinfunction "XTALO_121") (pintype "output"))
      (node (ref "Y1") (pin "2") (pinfunction "2_2") (pintype "passive"))
    )
    (net (code "107") (name "2.5V") (class "Default")
      (node (ref "C16") (pin "2") (pinfunction "2_2") (pintype "passive"))
      (node (ref "C17") (pin "2") (pinfunction "2_2") (pintype "passive"))
      (node (ref "C18") (pin "2") (pinfunction "2_2") (pintype "passive"))
      (node (ref "C19") (pin "2") (pinfunction "2_2") (pintype "passive"))
      (node (ref "C20") (pin "2") (pinfunction "2_2") (pintype "passive"))
      (node (ref "C21") (pin "2") (pinfunction "2_2") (pintype "passive"))
      (node (ref "C24") (pin "1") (pinfunction "1_1") (pintype "passive"))
      (node (ref "C5") (pin "2") (pinfunction "2_2") (pintype "passive"))
      (node (ref "C6") (pin "2") (pinfunction "2_2") (pintype "passive"))
      (node (ref "C7") (pin "2") (pinfunction "2_2") (pintype "passive"))
      (node (ref "C8") (pin "2") (pinfunction "2_2") (pintype "passive"))
      (node (ref "R1") (pin "2") (pinfunction "2_2") (pintype "passive"))
      (node (ref "R3") (pin "2") (pinfunction "2_2") (pintype "passive"))
      (node (ref "U1") (pin "1") (pinfunction "VDD1_1") (pintype "power_in"))
      (node (ref "U1") (pin "15") (pinfunction "VDDQ3_15") (pintype "power_in"))
      (node (ref "U1") (pin "18") (pinfunction "VDD2_18") (pintype "power_in"))
      (node (ref "U1") (pin "3") (pinfunction "VDDQ1_3") (pintype "power_in"))
      (node (ref "U1") (pin "33") (pinfunction "VDD3_33") (pintype "power_in"))
      (node (ref "U1") (pin "55") (pinfunction "VDDQ4_55") (pintype "power_in"))
      (node (ref "U1") (pin "61") (pinfunction "VDDQ5_61") (pintype "power_in"))
      (node (ref "U1") (pin "9") (pinfunction "VDDQ2_9") (pintype "power_in"))
      (node (ref "U2") (pin "106") (pinfunction "VDDM/LRADC4_106") (pintype "power_in"))
      (node (ref "U2") (pin "38") (pinfunction "VDDIO_EMIQ_38") (pintype "power_in"))
      (node (ref "U2") (pin "45") (pinfunction "VDDIO_EMI1_45") (pintype "power_in"))
      (node (ref "U2") (pin "53") (pinfunction "VDDIO_EMI2_53") (pintype "power_in"))
    )
    (net (code "108") (name "3.3V") (class "Default")
      (node (ref "C14") (pin "2") (pinfunction "2_2") (pintype "passive"))
      (node (ref "C15") (pin "2") (pinfunction "2_2") (pintype "passive"))
      (node (ref "C3") (pin "2") (pinfunction "2_2") (pintype "passive"))
      (node (ref "C4") (pin "2") (pinfunction "2_2") (pintype "passive"))
      (node (ref "D01_") (pin "2") (pinfunction "2_2") (pintype "passive"))
      (node (ref "D2") (pin "2") (pinfunction "2_2") (pintype "passive"))
      (node (ref "D3") (pin "2") (pinfunction "2_2") (pintype "passive"))
      (node (ref "D4") (pin "2") (pinfunction "2_2") (pintype "passive"))
      (node (ref "L2") (pin "1") (pinfunction "1_1") (pintype "passive"))
      (node (ref "R10") (pin "2") (pinfunction "2_2") (pintype "passive"))
      (node (ref "R11") (pin "2") (pinfunction "2_2") (pintype "passive"))
      (node (ref "R2") (pin "1") (pinfunction "1_1") (pintype "passive"))
      (node (ref "R7") (pin "2") (pinfunction "2_2") (pintype "passive"))
      (node (ref "R8") (pin "1") (pinfunction "1_1") (pintype "passive"))
      (node (ref "R9") (pin "2") (pinfunction "2_2") (pintype "passive"))
      (node (ref "RM3") (pin "1.2") (pinfunction "2_1.2") (pintype "passive"))
      (node (ref "RM3") (pin "3.2") (pinfunction "2_3.2") (pintype "passive"))
      (node (ref "RM3") (pin "4.2") (pinfunction "2_4.2") (pintype "passive"))
      (node (ref "U$1") (pin "2") (pinfunction "VCC_2") (pintype "bidirectional"))
      (node (ref "U2") (pin "18") (pinfunction "VDDIO33_1_18") (pintype "power_in"))
      (node (ref "U2") (pin "92") (pinfunction "VDDIO33_3_92") (pintype "power_in"))
      (node (ref "U2") (pin "95") (pinfunction "DCDC_VDDIO_95") (pintype "power_in"))
    )
    (net (code "110") (name "BAT") (class "Default")
      (node (ref "C25") (pin "2") (pinfunction "2_2") (pintype "passive"))
      (node (ref "C27") (pin "2") (pinfunction "2_2") (pintype "passive"))
      (node (ref "C28") (pin "2") (pinfunction "2_2") (pintype "passive"))
      (node (ref "D1") (pin "A") (pinfunction "A_A") (pintype "passive"))
      (node (ref "JP4") (pin "25") (pinfunction "25_25") (pintype "passive"))
      (node (ref "U2") (pin "100") (pinfunction "DCDC_BATTERY_100") (pintype "power_in"))
      (node (ref "U2") (pin "103") (pinfunction "BATT_103") (pintype "input"))
    )
    (net (code "111") (name "GND") (class "Default")
      (node (ref "C1") (pin "1") (pinfunction "1_1") (pintype "passive"))
      (node (ref "C10") (pin "1") (pinfunction "1_1") (pintype "passive"))
      (node (ref "C11") (pin "1") (pinfunction "1_1") (pintype "passive"))
      (node (ref "C12") (pin "1") (pinfunction "1_1") (pintype "passive"))
      (node (ref "C13") (pin "1") (pinfunction "1_1") (pintype "passive"))
      (node (ref "C14") (pin "1") (pinfunction "1_1") (pintype "passive"))
      (node (ref "C15") (pin "1") (pinfunction "1_1") (pintype "passive"))
      (node (ref "C16") (pin "1") (pinfunction "1_1") (pintype "passive"))
      (node (ref "C17") (pin "1") (pinfunction "1_1") (pintype "passive"))
      (node (ref "C18") (pin "1") (pinfunction "1_1") (pintype "passive"))
      (node (ref "C19") (pin "1") (pinfunction "1_1") (pintype "passive"))
      (node (ref "C2") (pin "1") (pinfunction "1_1") (pintype "passive"))
      (node (ref "C20") (pin "1") (pinfunction "1_1") (pintype "passive"))
      (node (ref "C21") (pin "1") (pinfunction "1_1") (pintype "passive"))
      (node (ref "C22") (pin "1") (pinfunction "1_1") (pintype "passive"))
      (node (ref "C23") (pin "1") (pinfunction "1_1") (pintype "passive"))
      (node (ref "C25") (pin "1") (pinfunction "1_1") (pintype "passive"))
      (node (ref "C26") (pin "1") (pinfunction "1_1") (pintype "passive"))
      (node (ref "C27") (pin "1") (pinfunction "1_1") (pintype "passive"))
      (node (ref "C28") (pin "1") (pinfunction "1_1") (pintype "passive"))
      (node (ref "C29") (pin "1") (pinfunction "1_1") (pintype "passive"))
      (node (ref "C3") (pin "1") (pinfunction "1_1") (pintype "passive"))
      (node (ref "C30") (pin "1") (pinfunction "1_1") (pintype "passive"))
      (node (ref "C31") (pin "1") (pinfunction "1_1") (pintype "passive"))
      (node (ref "C32") (pin "1") (pinfunction "1_1") (pintype "passive"))
      (node (ref "C33") (pin "1") (pinfunction "1_1") (pintype "passive"))
      (node (ref "C34") (pin "1") (pinfunction "1_1") (pintype "passive"))
      (node (ref "C35") (pin "1") (pinfunction "1_1") (pintype "passive"))
      (node (ref "C36") (pin "1") (pinfunction "1_1") (pintype "passive"))
      (node (ref "C37") (pin "1") (pinfunction "1_1") (pintype "passive"))
      (node (ref "C38") (pin "1") (pinfunction "1_1") (pintype "passive"))
      (node (ref "C4") (pin "1") (pinfunction "1_1") (pintype "passive"))
      (node (ref "C5") (pin "1") (pinfunction "1_1") (pintype "passive"))
      (node (ref "C6") (pin "1") (pinfunction "1_1") (pintype "passive"))
      (node (ref "C7") (pin "1") (pinfunction "1_1") (pintype "passive"))
      (node (ref "C8") (pin "1") (pinfunction "1_1") (pintype "passive"))
      (node (ref "C9") (pin "1") (pinfunction "1_1") (pintype "passive"))
      (node (ref "JP4") (pin "24") (pinfunction "24_24") (pintype "passive"))
      (node (ref "JP6") (pin "2") (pinfunction "2_2") (pintype "passive"))
      (node (ref "R4") (pin "1") (pinfunction "1_1") (pintype "passive"))
      (node (ref "R5") (pin "1") (pinfunction "1_1") (pintype "passive"))
      (node (ref "R6") (pin "2") (pinfunction "2_2") (pintype "passive"))
      (node (ref "RM2") (pin "1.2") (pinfunction "1.2_1.2") (pintype "passive"))
      (node (ref "RM2") (pin "2.2") (pinfunction "2.2_2.2") (pintype "passive"))
      (node (ref "RM2") (pin "3.2") (pinfunction "3.2_3.2") (pintype "passive"))
      (node (ref "RM2") (pin "4.2") (pinfunction "4.2_4.2") (pintype "passive"))
      (node (ref "SD") (pin "6") (pinfunction "VSS_6") (pintype "power_in"))
      (node (ref "U$1") (pin "10") (pinfunction "VSS_10") (pintype "bidirectional"))
      (node (ref "U1") (pin "12") (pinfunction "VSSQ2_12") (pintype "power_in"))
      (node (ref "U1") (pin "34") (pinfunction "VSS1_34") (pintype "power_in"))
      (node (ref "U1") (pin "48") (pinfunction "VSS2_48") (pintype "power_in"))
      (node (ref "U1") (pin "52") (pinfunction "VSSQ3_52") (pintype "power_in"))
      (node (ref "U1") (pin "58") (pinfunction "VSSQ4_58") (pintype "power_in"))
      (node (ref "U1") (pin "6") (pinfunction "VSSQ1_6") (pintype "power_in"))
      (node (ref "U1") (pin "64") (pinfunction "VSSQ5_64") (pintype "power_in"))
      (node (ref "U1") (pin "66") (pinfunction "VSS3_66") (pintype "power_in"))
      (node (ref "U2") (pin "105") (pinfunction "VSSA4_105") (pintype "power_in"))
      (node (ref "U2") (pin "112") (pinfunction "VSSA1_112") (pintype "power_in"))
      (node (ref "U2") (pin "118") (pinfunction "VSSA2_118") (pintype "power_in"))
      (node (ref "U2") (pin "30") (pinfunction "VSSD1_30") (pintype "power_in"))
      (node (ref "U2") (pin "35") (pinfunction "VSSD2_35") (pintype "power_in"))
      (node (ref "U2") (pin "98") (pinfunction "DCDC_GND_98") (pintype "power_in"))
      (node (ref "Y1") (pin "GND1") (pinfunction "G1_GND1") (pintype "bidirectional"))
      (node (ref "Y1") (pin "GND2") (pinfunction "G2_GND2") (pintype "bidirectional"))
    )
    (net (code "112") (name "Net-(D1-C)") (class "Default")
      (node (ref "C10") (pin "2") (pinfunction "2_2") (pintype "passive"))
      (node (ref "C9") (pin "2") (pinfunction "2_2") (pintype "passive"))
      (node (ref "D1") (pin "K") (pinfunction "C_K") (pintype "passive"))
      (node (ref "U2") (pin "101") (pinfunction "VDD4P2_101") (pintype "power_in"))
    )
    (net (code "113") (name "Net-(D01_-Pad1)") (class "Default")
      (node (ref "D01_") (pin "1") (pinfunction "1_1") (pintype "passive"))
      (node (ref "RM1") (pin "2.1") (pinfunction "2.1_2.1") (pintype "passive"))
    )
    (net (code "114") (name "Net-(D2-Pad1)") (class "Default")
      (node (ref "D2") (pin "1") (pinfunction "1_1") (pintype "passive"))
      (node (ref "RM1") (pin "4.1") (pinfunction "4.1_4.1") (pintype "passive"))
    )
    (net (code "115") (name "Net-(D3-Pad1)") (class "Default")
      (node (ref "D3") (pin "1") (pinfunction "1_1") (pintype "passive"))
      (node (ref "RM1") (pin "3.1") (pinfunction "3.1_3.1") (pintype "passive"))
    )
    (net (code "116") (name "Net-(D4-Pad1)") (class "Default")
      (node (ref "D4") (pin "1") (pinfunction "1_1") (pintype "passive"))
      (node (ref "RM1") (pin "1.1") (pinfunction "1.1_1.1") (pintype "passive"))
    )
    (net (code "117") (name "Net-(LED1-PadC)") (class "Default")
      (node (ref "LED1") (pin "C") (pinfunction "C_C") (pintype "passive"))
      (node (ref "R5") (pin "2") (pinfunction "2_2") (pintype "passive"))
    )
    (net (code "118") (name "Net-(U1-VREF)") (class "Default")
      (node (ref "C24") (pin "2") (pinfunction "2_2") (pintype "passive"))
      (node (ref "C26") (pin "2") (pinfunction "2_2") (pintype "passive"))
      (node (ref "R3") (pin "1") (pinfunction "1_1") (pintype "passive"))
      (node (ref "R4") (pin "2") (pinfunction "2_2") (pintype "passive"))
      (node (ref "U1") (pin "49") (pinfunction "VREF_49") (pintype "input"))
    )
    (net (code "119") (name "Net-(U2-DCDC_LN1)") (class "Default")
      (node (ref "C29") (pin "2") (pinfunction "2_2") (pintype "passive"))
      (node (ref "L1") (pin "2") (pinfunction "2_2") (pintype "passive"))
      (node (ref "U2") (pin "97") (pinfunction "DCDC_LN1_97") (pintype "passive"))
    )
    (net (code "120") (name "Net-(U2-DCDC_LP)") (class "Default")
      (node (ref "C30") (pin "2") (pinfunction "2_2") (pintype "passive"))
      (node (ref "L1") (pin "1") (pinfunction "1_1") (pintype "passive"))
      (node (ref "U2") (pin "99") (pinfunction "DCDC_LP_99") (pintype "passive"))
    )
    (net (code "121") (name "Net-(U2-VAG)") (class "Default")
      (node (ref "C35") (pin "2") (pinfunction "2_2") (pintype "passive"))
      (node (ref "U2") (pin "117") (pinfunction "VAG_117") (pintype "passive"))
    )
    (net (code "122") (name "unconnected-(U$1-DNU-Pad4)") (class "Default")
      (node (ref "U$1") (pin "4") (pinfunction "DNU_4") (pintype "bidirectional"))
    )
    (net (code "123") (name "unconnected-(U$1-DNU2-Pad5)") (class "Default")
      (node (ref "U$1") (pin "5") (pinfunction "DNU2_5") (pintype "bidirectional"))
    )
    (net (code "124") (name "unconnected-(U$1-DNU3-Pad12)") (class "Default")
      (node (ref "U$1") (pin "12") (pinfunction "DNU3_12") (pintype "bidirectional"))
    )
    (net (code "125") (name "unconnected-(U$1-DNU4-Pad11)") (class "Default")
      (node (ref "U$1") (pin "11") (pinfunction "DNU4_11") (pintype "bidirectional"))
    )
    (net (code "126") (name "unconnected-(U$1-HOLD-Pad1)") (class "Default")
      (node (ref "U$1") (pin "1") (pinfunction "HOLD_1") (pintype "bidirectional"))
    )
    (net (code "127") (name "unconnected-(U$1-NC-Pad13)") (class "Default")
      (node (ref "U$1") (pin "13") (pinfunction "NC_13") (pintype "bidirectional"))
    )
    (net (code "128") (name "unconnected-(U$1-RESET-Pad3)") (class "Default")
      (node (ref "U$1") (pin "3") (pinfunction "RESET_3") (pintype "bidirectional"))
    )
    (net (code "129") (name "unconnected-(U$1-VIO{slash}RFU-Pad14)") (class "Default")
      (node (ref "U$1") (pin "14") (pinfunction "VIO/RFU_14") (pintype "bidirectional"))
    )
    (net (code "130") (name "unconnected-(U$1-WP-Pad9)") (class "Default")
      (node (ref "U$1") (pin "9") (pinfunction "WP_9") (pintype "bidirectional"))
    )
    (net (code "131") (name "unconnected-(U1-NC1-Pad14)") (class "Default")
      (node (ref "U1") (pin "14") (pinfunction "NC1_14") (pintype "no_connect"))
    )
    (net (code "132") (name "unconnected-(U1-NC2-Pad17)") (class "Default")
      (node (ref "U1") (pin "17") (pinfunction "NC2_17") (pintype "no_connect"))
    )
    (net (code "133") (name "unconnected-(U1-NC3-Pad19)") (class "Default")
      (node (ref "U1") (pin "19") (pinfunction "NC3_19") (pintype "no_connect"))
    )
    (net (code "134") (name "unconnected-(U1-NC4-Pad25)") (class "Default")
      (node (ref "U1") (pin "25") (pinfunction "NC4_25") (pintype "no_connect"))
    )
    (net (code "135") (name "unconnected-(U1-NC5-Pad43)") (class "Default")
      (node (ref "U1") (pin "43") (pinfunction "NC5_43") (pintype "no_connect"))
    )
    (net (code "136") (name "unconnected-(U1-NC6-Pad50)") (class "Default")
      (node (ref "U1") (pin "50") (pinfunction "NC6_50") (pintype "no_connect"))
    )
    (net (code "137") (name "unconnected-(U1-NC7-Pad53)") (class "Default")
      (node (ref "U1") (pin "53") (pinfunction "NC7_53") (pintype "no_connect"))
    )
    (net (code "138") (name "unconnected-(U2-VDAC1-Pad104)") (class "Default")
      (node (ref "U2") (pin "104") (pinfunction "VDAC1_104") (pintype "output"))
    )
  )
)
